# interrupcion_de_bomba_2.net
KiCad netlist of a schematic drawn in EAGLE
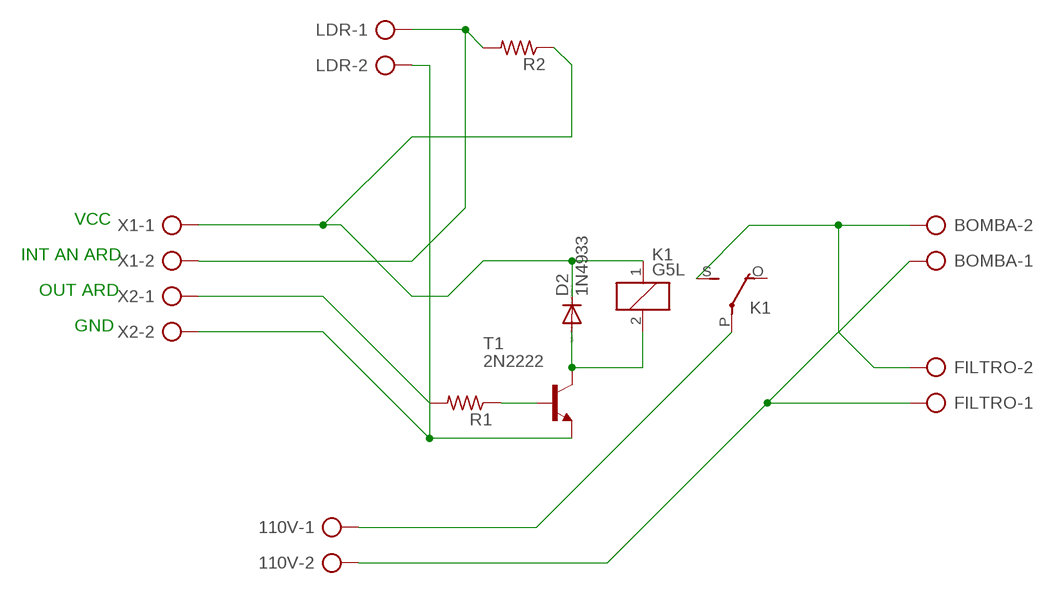
[diagram p0: schematic, sheet 1]

(export (version "E")
  (design (tool "Eeschema 10.0.6"))
  (components
    (comp (ref "110V")
      (value "AK500/2-H")
      (footprint "eagle-import:AK500_2-H")
      (libsource (lib "eagle-import") (part "AK500/2-H"))
    )
    (comp (ref "BOMBA")
      (value "AK500/2-H")
      (footprint "eagle-import:AK500_2-H")
      (libsource (lib "eagle-import") (part "AK500/2-H"))
    )
    (comp (ref "D2")
      (value "1N4933")
      (footprint "eagle-import:DO41-10")
      (libsource (lib "eagle-import") (part "1N4933"))
    )
    (comp (ref "FILTRO")
      (value "AK500/2-H")
      (footprint "eagle-import:AK500_2-H")
      (libsource (lib "eagle-import") (part "AK500/2-H"))
    )
    (comp (ref "K1")
      (value "G5L")
      (footprint "eagle-import:G5LE")
      (libsource (lib "eagle-import") (part "G5L"))
    )
    (comp (ref "LDR")
      (value "AK500/2-H")
      (footprint "eagle-import:AK500_2-H")
      (libsource (lib "eagle-import") (part "AK500/2-H"))
    )
    (comp (ref "R1")
      (value "R-US_0207/10")
      (footprint "eagle-import:0207_10")
      (libsource (lib "eagle-import") (part "R-US_0207/10"))
    )
    (comp (ref "R2")
      (value "R-US_0207/10")
      (footprint "eagle-import:0207_10")
      (libsource (lib "eagle-import") (part "R-US_0207/10"))
    )
    (comp (ref "T1")
      (value "2N2222")
      (footprint "eagle-import:TO18")
      (libsource (lib "eagle-import") (part "2N2222"))
    )
    (comp (ref "X1")
      (value "AK500/2-H")
      (footprint "eagle-import:AK500_2-H")
      (libsource (lib "eagle-import") (part "AK500/2-H"))
    )
    (comp (ref "X2")
      (value "AK500/2-H")
      (footprint "eagle-import:AK500_2-H")
      (libsource (lib "eagle-import") (part "AK500/2-H"))
    )
  )
  (nets
    (net (code "1") (name "Net-(110VA-KL)") (class "Default")
      (node (ref "110V") (pin "1") (pinfunction "KL_1") (pintype "passive"))
      (node (ref "K1") (pin "P") (pinfunction "P_P") (pintype "passive"))
    )
    (net (code "2") (name "Net-(110VB-KL)") (class "Default")
      (node (ref "110V") (pin "2") (pinfunction "KL_2") (pintype "passive"))
      (node (ref "BOMBA") (pin "1") (pinfunction "KL_1") (pintype "passive"))
      (node (ref "FILTRO") (pin "1") (pinfunction "KL_1") (pintype "passive"))
    )
    (net (code "3") (name "Net-(BOMBAB-KL)") (class "Default")
      (node (ref "BOMBA") (pin "2") (pinfunction "KL_2") (pintype "passive"))
      (node (ref "FILTRO") (pin "2") (pinfunction "KL_2") (pintype "passive"))
      (node (ref "K1") (pin "S") (pinfunction "S_S") (pintype "passive"))
    )
    (net (code "4") (name "Net-(LDRA-KL)") (class "Default")
      (node (ref "LDR") (pin "1") (pinfunction "KL_1") (pintype "passive"))
      (node (ref "R2") (pin "2") (pinfunction "2_2") (pintype "passive"))
      (node (ref "X1") (pin "2") (pinfunction "KL_2") (pintype "passive"))
    )
    (net (code "5") (name "Net-(LDRB-KL)") (class "Default")
      (node (ref "LDR") (pin "2") (pinfunction "KL_2") (pintype "passive"))
      (node (ref "T1") (pin "1") (pinfunction "E_1") (pintype "passive"))
      (node (ref "X2") (pin "2") (pinfunction "KL_2") (pintype "passive"))
    )
    (net (code "6") (name "Net-(T1-B)") (class "Default")
      (node (ref "R1") (pin "1") (pinfunction "1_1") (pintype "passive"))
      (node (ref "T1") (pin "2") (pinfunction "B_2") (pintype "passive"))
    )
    (net (code "7") (name "Net-(T1-C)") (class "Default")
      (node (ref "D2") (pin "A") (pinfunction "A_A") (pintype "passive"))
      (node (ref "K1") (pin "2") (pinfunction "2_2") (pintype "passive"))
      (node (ref "T1") (pin "3") (pinfunction "C_3") (pintype "passive"))
    )
    (net (code "8") (name "Net-(X1A-KL)") (class "Default")
      (node (ref "D2") (pin "C") (pinfunction "C_C") (pintype "passive"))
      (node (ref "K1") (pin "1") (pinfunction "1_1") (pintype "passive"))
      (node (ref "R2") (pin "1") (pinfunction "1_1") (pintype "passive"))
      (node (ref "X1") (pin "1") (pinfunction "KL_1") (pintype "passive"))
    )
    (net (code "9") (name "Net-(X2A-KL)") (class "Default")
      (node (ref "R1") (pin "2") (pinfunction "2_2") (pintype "passive"))
      (node (ref "X2") (pin "1") (pinfunction "KL_1") (pintype "passive"))
    )
    (net (code "10") (name "unconnected-(K1-PadO)") (class "Default")
      (node (ref "K1") (pin "O") (pinfunction "O_O") (pintype "passive"))
    )
  )
)
